# DTMF.net
KiCad netlist of a schematic drawn in Altium Designer
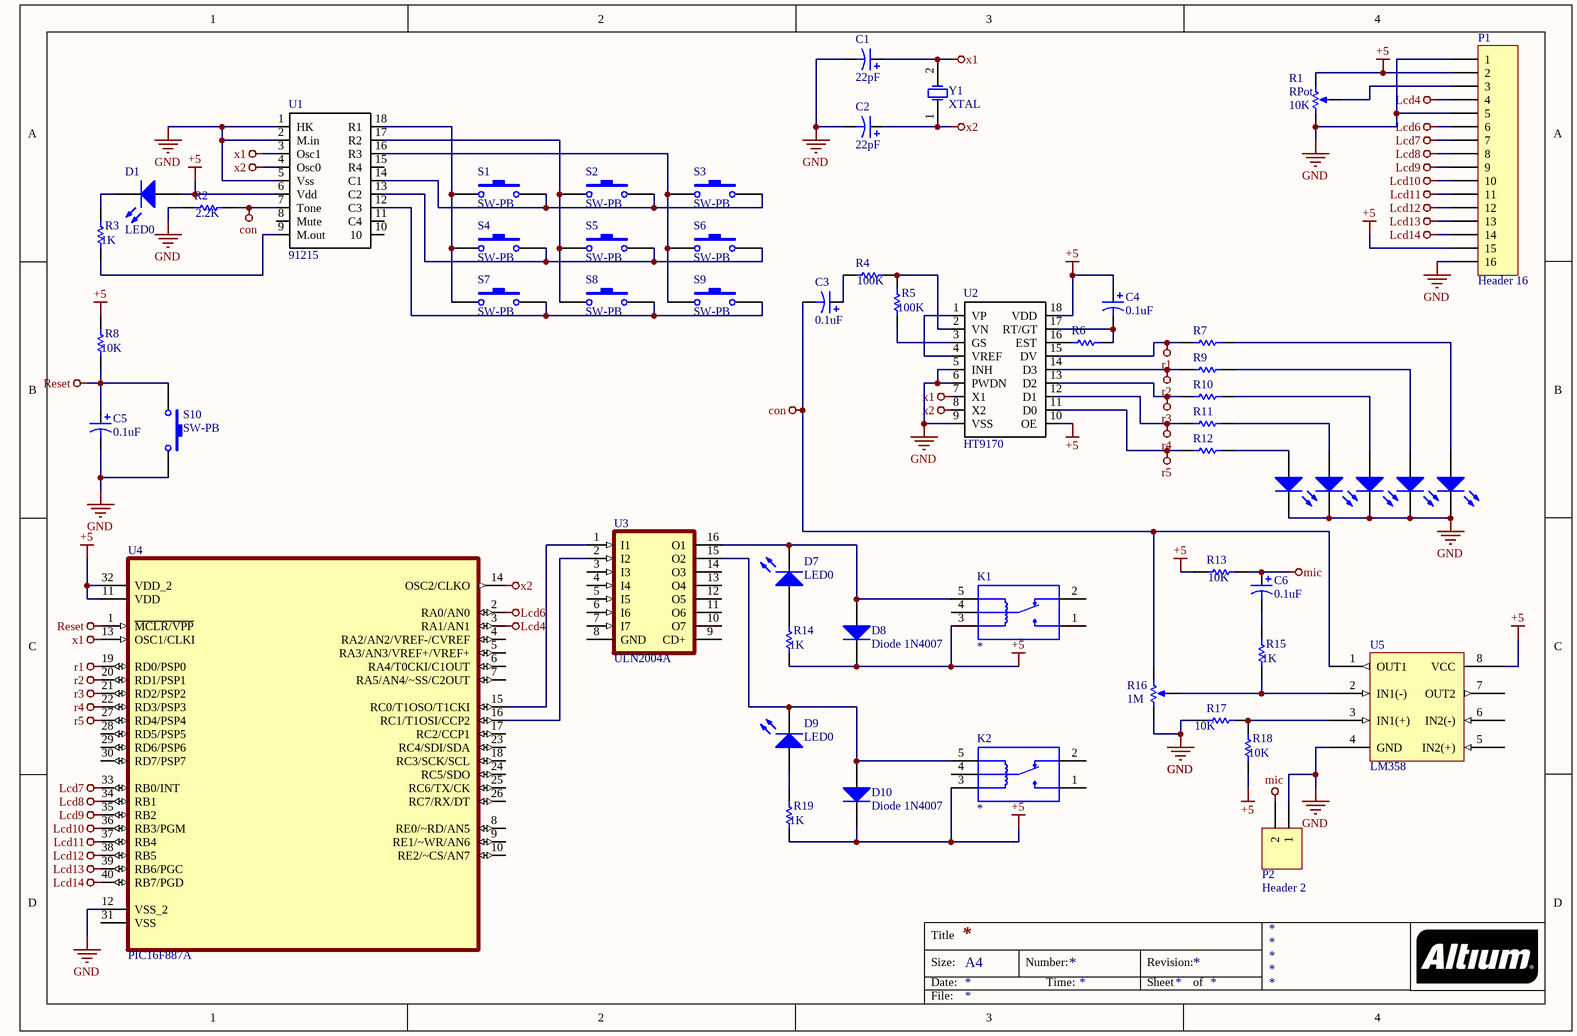
[diagram p0: DTMF.SchDoc]

(export (version "E")
  (design (tool "Eeschema 10.0.6"))
  (components
    (comp (ref "C1")
      (value "22pF")
      (footprint "capacitor")
      (fields (field (name "Comment") "cap"))
      (libsource (lib "capacitor") (part "cap"))
    )
    (comp (ref "C2")
      (value "22pF")
      (footprint "capacitor")
      (fields (field (name "Comment") "cap"))
      (libsource (lib "capacitor") (part "cap"))
    )
    (comp (ref "C3")
      (value "0.1uF")
      (footprint "capacitor")
      (fields (field (name "Comment") "cap"))
      (libsource (lib "capacitor") (part "cap"))
    )
    (comp (ref "C4")
      (value "0.1uF")
      (footprint "capacitor")
      (fields (field (name "Comment") "cap"))
      (libsource (lib "capacitor") (part "cap"))
    )
    (comp (ref "C5")
      (value "0.1uF")
      (footprint "capacitor")
      (fields (field (name "Comment") "cap"))
      (libsource (lib "capacitor") (part "cap"))
    )
    (comp (ref "C6")
      (value "0.1uF")
      (footprint "capacitor")
      (fields (field (name "Comment") "cap"))
      (libsource (lib "capacitor") (part "cap"))
    )
    (comp (ref "D1")
      (value "LED0")
      (footprint "LED-0")
      (description "Typical INFRARED GaAs LED")
      (fields (field (name "PUBLISHER") "Altium Limited"))
      (libsource (lib "Miscellaneous Devices") (part "LED0"))
    )
    (comp (ref "D2")
      (value "LED0")
      (footprint "LED-0")
      (description "Typical INFRARED GaAs LED")
      (fields (field (name "PUBLISHER") "Altium Limited"))
      (libsource (lib "Miscellaneous Devices") (part "LED0"))
    )
    (comp (ref "D3")
      (value "LED0")
      (footprint "LED-0")
      (description "Typical INFRARED GaAs LED")
      (fields (field (name "PUBLISHER") "Altium Limited"))
      (libsource (lib "Miscellaneous Devices") (part "LED0"))
    )
    (comp (ref "D4")
      (value "LED0")
      (footprint "LED-0")
      (description "Typical INFRARED GaAs LED")
      (fields (field (name "PUBLISHER") "Altium Limited"))
      (libsource (lib "Miscellaneous Devices") (part "LED0"))
    )
    (comp (ref "D5")
      (value "LED0")
      (footprint "LED-0")
      (description "Typical INFRARED GaAs LED")
      (fields (field (name "PUBLISHER") "Altium Limited"))
      (libsource (lib "Miscellaneous Devices") (part "LED0"))
    )
    (comp (ref "D6")
      (value "LED0")
      (footprint "LED-0")
      (description "Typical INFRARED GaAs LED")
      (fields (field (name "PUBLISHER") "Altium Limited"))
      (libsource (lib "Miscellaneous Devices") (part "LED0"))
    )
    (comp (ref "D7")
      (value "LED0")
      (footprint "LED-0")
      (description "Typical INFRARED GaAs LED")
      (fields (field (name "PUBLISHER") "Altium Limited"))
      (libsource (lib "Miscellaneous Devices") (part "LED0"))
    )
    (comp (ref "D8")
      (value "Diode 1N4007")
      (footprint "DO-41")
      (description "1 Amp General Purpose Rectifier")
      (fields (field (name "PUBLISHER") "Altium Limited"))
      (libsource (lib "Miscellaneous Devices") (part "Diode 1N4007"))
    )
    (comp (ref "D9")
      (value "LED0")
      (footprint "LED-0")
      (description "Typical INFRARED GaAs LED")
      (fields (field (name "PUBLISHER") "Altium Limited"))
      (libsource (lib "Miscellaneous Devices") (part "LED0"))
    )
    (comp (ref "D10")
      (value "Diode 1N4007")
      (footprint "DO-41")
      (description "1 Amp General Purpose Rectifier")
      (fields (field (name "PUBLISHER") "Altium Limited"))
      (libsource (lib "Miscellaneous Devices") (part "Diode 1N4007"))
    )
    (comp (ref "K1")
      (value "1-1721150-0")
      (footprint "SnapEDApcb:RELAY_ORWH-SH-105D1F,000")
      (description "Electromechanical Relay 5VDC 15A SPDT __ 19.2mm 15.5mm 15mm__ THT General Purpose Relay")
      (fields
        (field (name "MP") "ORWH-SH-105D1F,000")
        (field (name "MF") "TE Connectivity")
        (field (name "COMMENT_1") "*")
      )
      (libsource (lib "SnapEDAsch") (part "ORWH-SH-105D1F,000"))
    )
    (comp (ref "K2")
      (value "1-1721150-0")
      (footprint "SnapEDApcb:RELAY_ORWH-SH-105D1F,000")
      (description "Electromechanical Relay 5VDC 15A SPDT __ 19.2mm 15.5mm 15mm__ THT General Purpose Relay")
      (fields
        (field (name "MP") "ORWH-SH-105D1F,000")
        (field (name "MF") "TE Connectivity")
        (field (name "COMMENT_1") "*")
      )
      (libsource (lib "SnapEDAsch") (part "ORWH-SH-105D1F,000"))
    )
    (comp (ref "P1")
      (value "Header 16")
      (footprint "HDR1X16")
      (description "Header, 16-Pin")
      (fields (field (name "PUBLISHER") "Altium Limited"))
      (libsource (lib "Miscellaneous Connectors") (part "Header 16"))
    )
    (comp (ref "P2")
      (value "Header 2")
      (footprint "HDR1X2")
      (description "Header, 2-Pin")
      (fields (field (name "PUBLISHER") "Altium Limited"))
      (libsource (lib "Miscellaneous Connectors") (part "Header 2"))
    )
    (comp (ref "R1")
      (value "RPot")
      (footprint "VR5")
      (description "Potentiometer")
      (fields (field (name "ALTIUM_VALUE") "10K") (field (name "PUBLISHER") "Altium Limited"))
      (libsource (lib "Miscellaneous Devices") (part "RPot"))
    )
    (comp (ref "R2")
      (value "2.2K")
      (footprint "AXIAL-0.3")
      (description "Resistor")
      (fields (field (name "Comment") "Res1") (field (name "PUBLISHER") "Altium Limited"))
      (libsource (lib "Miscellaneous Devices") (part "Res1"))
    )
    (comp (ref "R3")
      (value "1K")
      (footprint "AXIAL-0.3")
      (description "Resistor")
      (fields (field (name "Comment") "Res1") (field (name "PUBLISHER") "Altium Limited"))
      (libsource (lib "Miscellaneous Devices") (part "Res1"))
    )
    (comp (ref "R4")
      (value "100K")
      (footprint "AXIAL-0.3")
      (description "Resistor")
      (fields (field (name "Comment") "Res1") (field (name "PUBLISHER") "Altium Limited"))
      (libsource (lib "Miscellaneous Devices") (part "Res1"))
    )
    (comp (ref "R5")
      (value "100K")
      (footprint "AXIAL-0.3")
      (description "Resistor")
      (fields (field (name "Comment") "Res1") (field (name "PUBLISHER") "Altium Limited"))
      (libsource (lib "Miscellaneous Devices") (part "Res1"))
    )
    (comp (ref "R6")
      (value "Res1")
      (footprint "AXIAL-0.3")
      (description "Resistor")
      (fields (field (name "PUBLISHER") "Altium Limited"))
      (libsource (lib "Miscellaneous Devices") (part "Res1"))
    )
    (comp (ref "R7")
      (value "Res1")
      (footprint "AXIAL-0.3")
      (description "Resistor")
      (fields (field (name "PUBLISHER") "Altium Limited"))
      (libsource (lib "Miscellaneous Devices") (part "Res1"))
    )
    (comp (ref "R8")
      (value "10K")
      (footprint "AXIAL-0.3")
      (description "Resistor")
      (fields (field (name "Comment") "Res1") (field (name "PUBLISHER") "Altium Limited"))
      (libsource (lib "Miscellaneous Devices") (part "Res1"))
    )
    (comp (ref "R9")
      (value "Res1")
      (footprint "AXIAL-0.3")
      (description "Resistor")
      (fields (field (name "PUBLISHER") "Altium Limited"))
      (libsource (lib "Miscellaneous Devices") (part "Res1"))
    )
    (comp (ref "R10")
      (value "Res1")
      (footprint "AXIAL-0.3")
      (description "Resistor")
      (fields (field (name "PUBLISHER") "Altium Limited"))
      (libsource (lib "Miscellaneous Devices") (part "Res1"))
    )
    (comp (ref "R11")
      (value "Res1")
      (footprint "AXIAL-0.3")
      (description "Resistor")
      (fields (field (name "PUBLISHER") "Altium Limited"))
      (libsource (lib "Miscellaneous Devices") (part "Res1"))
    )
    (comp (ref "R12")
      (value "Res1")
      (footprint "AXIAL-0.3")
      (description "Resistor")
      (fields (field (name "PUBLISHER") "Altium Limited"))
      (libsource (lib "Miscellaneous Devices") (part "Res1"))
    )
    (comp (ref "R13")
      (value "10K")
      (footprint "AXIAL-0.3")
      (description "Resistor")
      (fields (field (name "Comment") "Res1") (field (name "PUBLISHER") "Altium Limited"))
      (libsource (lib "Miscellaneous Devices") (part "Res1"))
    )
    (comp (ref "R14")
      (value "1K")
      (footprint "AXIAL-0.3")
      (description "Resistor")
      (fields (field (name "Comment") "Res1") (field (name "PUBLISHER") "Altium Limited"))
      (libsource (lib "Miscellaneous Devices") (part "Res1"))
    )
    (comp (ref "R15")
      (value "1K")
      (footprint "AXIAL-0.3")
      (description "Resistor")
      (fields (field (name "Comment") "Res1") (field (name "PUBLISHER") "Altium Limited"))
      (libsource (lib "Miscellaneous Devices") (part "Res1"))
    )
    (comp (ref "R16")
      (value "1M")
      (footprint "VR5")
      (description "Potentiometer")
      (fields (field (name "Comment") "RPot") (field (name "PUBLISHER") "Altium Limited"))
      (libsource (lib "Miscellaneous Devices") (part "RPot"))
    )
    (comp (ref "R17")
      (value "10K")
      (footprint "AXIAL-0.3")
      (description "Resistor")
      (fields (field (name "Comment") "Res1") (field (name "PUBLISHER") "Altium Limited"))
      (libsource (lib "Miscellaneous Devices") (part "Res1"))
    )
    (comp (ref "R18")
      (value "10K")
      (footprint "AXIAL-0.3")
      (description "Resistor")
      (fields (field (name "Comment") "Res1") (field (name "PUBLISHER") "Altium Limited"))
      (libsource (lib "Miscellaneous Devices") (part "Res1"))
    )
    (comp (ref "R19")
      (value "1K")
      (footprint "AXIAL-0.3")
      (description "Resistor")
      (fields (field (name "Comment") "Res1") (field (name "PUBLISHER") "Altium Limited"))
      (libsource (lib "Miscellaneous Devices") (part "Res1"))
    )
    (comp (ref "S1")
      (value "SW-PB")
      (footprint "SPST-2")
      (description "Switch")
      (fields (field (name "PUBLISHER") "Altium Limited"))
      (libsource (lib "Miscellaneous Devices") (part "SW-PB"))
    )
    (comp (ref "S2")
      (value "SW-PB")
      (footprint "SPST-2")
      (description "Switch")
      (fields (field (name "PUBLISHER") "Altium Limited"))
      (libsource (lib "Miscellaneous Devices") (part "SW-PB"))
    )
    (comp (ref "S3")
      (value "SW-PB")
      (footprint "SPST-2")
      (description "Switch")
      (fields (field (name "PUBLISHER") "Altium Limited"))
      (libsource (lib "Miscellaneous Devices") (part "SW-PB"))
    )
    (comp (ref "S4")
      (value "SW-PB")
      (footprint "SPST-2")
      (description "Switch")
      (fields (field (name "PUBLISHER") "Altium Limited"))
      (libsource (lib "Miscellaneous Devices") (part "SW-PB"))
    )
    (comp (ref "S5")
      (value "SW-PB")
      (footprint "SPST-2")
      (description "Switch")
      (fields (field (name "PUBLISHER") "Altium Limited"))
      (libsource (lib "Miscellaneous Devices") (part "SW-PB"))
    )
    (comp (ref "S6")
      (value "SW-PB")
      (footprint "SPST-2")
      (description "Switch")
      (fields (field (name "PUBLISHER") "Altium Limited"))
      (libsource (lib "Miscellaneous Devices") (part "SW-PB"))
    )
    (comp (ref "S7")
      (value "SW-PB")
      (footprint "SPST-2")
      (description "Switch")
      (fields (field (name "PUBLISHER") "Altium Limited"))
      (libsource (lib "Miscellaneous Devices") (part "SW-PB"))
    )
    (comp (ref "S8")
      (value "SW-PB")
      (footprint "SPST-2")
      (description "Switch")
      (fields (field (name "PUBLISHER") "Altium Limited"))
      (libsource (lib "Miscellaneous Devices") (part "SW-PB"))
    )
    (comp (ref "S9")
      (value "SW-PB")
      (footprint "SPST-2")
      (description "Switch")
      (fields (field (name "PUBLISHER") "Altium Limited"))
      (libsource (lib "Miscellaneous Devices") (part "SW-PB"))
    )
    (comp (ref "S10")
      (value "SW-PB")
      (footprint "SPST-2")
      (description "Switch")
      (fields (field (name "PUBLISHER") "Altium Limited"))
      (libsource (lib "Miscellaneous Devices") (part "SW-PB"))
    )
    (comp (ref "U1") (value "91215") (footprint "HT9170") (libsource (lib "Schlib1") (part "91215")))
    (comp (ref "U2")
      (value "HT9170")
      (footprint "HT9170")
      (fields (field (name "MF") "Holtek") (field (name "MP") "HT9170B"))
      (libsource (lib "HT9170") (part "HT9170"))
    )
    (comp (ref "U3")
      (value "ULN2004A")
      (footprint "ULN2004A:ULN2004A")
      (fields (field (name "MF") "STMicroelectronics"))
      (libsource (lib "SnapEDAsch") (part "ULN2004A"))
    )
    (comp (ref "U4")
      (value "PIC16F887A")
      (footprint "PIC16F887A")
      (description "PIC PICÂ® 16F Microcontroller IC 8-Bit 20MHz 14KB _8K x 14_ FLASH 40-PDIP")
      (fields (field (name "MP") "PIC16F877A-I/P") (field (name "MF") "Microchip"))
      (libsource (lib "SnapEDAsch") (part "PIC16F877A-I/P"))
    )
    (comp (ref "U5") (value "LM358") (footprint "LM358") (libsource (lib "LM358") (part "LM358")))
    (comp (ref "Y1")
      (value "XTAL")
      (footprint "R38")
      (description "Crystal Oscillator")
      (fields (field (name "PUBLISHER") "Altium Limited"))
      (libsource (lib "Miscellaneous Devices") (part "XTAL"))
    )
  )
  (nets
    (net (code "1") (name "+5") (class "Default")
      (node (ref "C4") (pin "1") (pinfunction "1_1") (pintype "passive"))
      (node (ref "D1") (pin "1") (pinfunction "A_1") (pintype "passive"))
      (node (ref "D10") (pin "2") (pinfunction "K_2") (pintype "passive"))
      (node (ref "D8") (pin "2") (pinfunction "K_2") (pintype "passive"))
      (node (ref "K1") (pin "3") (pinfunction "C1_3") (pintype "passive"))
      (node (ref "K2") (pin "3") (pinfunction "C1_3") (pintype "passive"))
      (node (ref "P1") (pin "15") (pinfunction "15_15") (pintype "passive"))
      (node (ref "P1") (pin "2") (pinfunction "2_2") (pintype "passive"))
      (node (ref "R1") (pin "2") (pinfunction "BOT_2") (pintype "passive"))
      (node (ref "R13") (pin "1") (pinfunction "1_1") (pintype "passive"))
      (node (ref "R14") (pin "1") (pinfunction "1_1") (pintype "passive"))
      (node (ref "R18") (pin "1") (pinfunction "1_1") (pintype "passive"))
      (node (ref "R19") (pin "1") (pinfunction "1_1") (pintype "passive"))
      (node (ref "R8") (pin "2") (pinfunction "2_2") (pintype "passive"))
      (node (ref "U1") (pin "6") (pinfunction "Vdd_6") (pintype "passive"))
      (node (ref "U2") (pin "10") (pinfunction "OE_10") (pintype "bidirectional"))
      (node (ref "U2") (pin "18") (pinfunction "VDD_18") (pintype "power_in"))
      (node (ref "U4") (pin "11") (pinfunction "VDD_11") (pintype "power_in"))
      (node (ref "U4") (pin "32") (pinfunction "VDD_2_32") (pintype "power_in"))
      (node (ref "U5") (pin "8") (pinfunction "VCC_8") (pintype "passive"))
    )
    (net (code "2") (name "GND") (class "Default")
      (node (ref "C1") (pin "2") (pinfunction "2_2") (pintype "passive"))
      (node (ref "C2") (pin "2") (pinfunction "2_2") (pintype "passive"))
      (node (ref "C5") (pin "2") (pinfunction "2_2") (pintype "passive"))
      (node (ref "D2") (pin "2") (pinfunction "K_2") (pintype "passive"))
      (node (ref "D3") (pin "2") (pinfunction "K_2") (pintype "passive"))
      (node (ref "D4") (pin "2") (pinfunction "K_2") (pintype "passive"))
      (node (ref "D5") (pin "2") (pinfunction "K_2") (pintype "passive"))
      (node (ref "D6") (pin "2") (pinfunction "K_2") (pintype "passive"))
      (node (ref "P1") (pin "1") (pinfunction "1_1") (pintype "passive"))
      (node (ref "P1") (pin "16") (pinfunction "16_16") (pintype "passive"))
      (node (ref "P1") (pin "5") (pinfunction "5_5") (pintype "passive"))
      (node (ref "P2") (pin "1") (pinfunction "1_1") (pintype "passive"))
      (node (ref "R1") (pin "1") (pinfunction "TOP_1") (pintype "passive"))
      (node (ref "R16") (pin "1") (pinfunction "TOP_1") (pintype "passive"))
      (node (ref "R17") (pin "1") (pinfunction "1_1") (pintype "passive"))
      (node (ref "R2") (pin "1") (pinfunction "1_1") (pintype "passive"))
      (node (ref "S10") (pin "2") (pinfunction "2_2") (pintype "passive"))
      (node (ref "U1") (pin "1") (pinfunction "HK_1") (pintype "passive"))
      (node (ref "U1") (pin "2") (pinfunction "M.in_2") (pintype "passive"))
      (node (ref "U1") (pin "5") (pinfunction "Vss_5") (pintype "passive"))
      (node (ref "U2") (pin "5") (pinfunction "INH_5") (pintype "bidirectional"))
      (node (ref "U2") (pin "6") (pinfunction "PWDN_6") (pintype "bidirectional"))
      (node (ref "U2") (pin "9") (pinfunction "VSS_9") (pintype "power_in"))
      (node (ref "U4") (pin "12") (pinfunction "VSS_2_12") (pintype "power_in"))
      (node (ref "U5") (pin "4") (pinfunction "GND_4") (pintype "passive"))
    )
    (net (code "3") (name "Lcd4") (class "Default")
      (node (ref "P1") (pin "4") (pinfunction "4_4") (pintype "passive"))
      (node (ref "U4") (pin "3") (pinfunction "RA1/AN1_3") (pintype "bidirectional"))
    )
    (net (code "4") (name "Lcd6") (class "Default")
      (node (ref "P1") (pin "6") (pinfunction "6_6") (pintype "passive"))
      (node (ref "U4") (pin "2") (pinfunction "RA0/AN0_2") (pintype "bidirectional"))
    )
    (net (code "5") (name "Lcd7") (class "Default")
      (node (ref "P1") (pin "7") (pinfunction "7_7") (pintype "passive"))
      (node (ref "U4") (pin "33") (pinfunction "RB0/INT_33") (pintype "bidirectional"))
    )
    (net (code "6") (name "Lcd8") (class "Default")
      (node (ref "P1") (pin "8") (pinfunction "8_8") (pintype "passive"))
      (node (ref "U4") (pin "34") (pinfunction "RB1_34") (pintype "bidirectional"))
    )
    (net (code "7") (name "Lcd9") (class "Default")
      (node (ref "P1") (pin "9") (pinfunction "9_9") (pintype "passive"))
      (node (ref "U4") (pin "35") (pinfunction "RB2_35") (pintype "bidirectional"))
    )
    (net (code "8") (name "Lcd10") (class "Default")
      (node (ref "P1") (pin "10") (pinfunction "10_10") (pintype "passive"))
      (node (ref "U4") (pin "36") (pinfunction "RB3/PGM_36") (pintype "bidirectional"))
    )
    (net (code "9") (name "Lcd11") (class "Default")
      (node (ref "P1") (pin "11") (pinfunction "11_11") (pintype "passive"))
      (node (ref "U4") (pin "37") (pinfunction "RB4_37") (pintype "bidirectional"))
    )
    (net (code "10") (name "Lcd12") (class "Default")
      (node (ref "P1") (pin "12") (pinfunction "12_12") (pintype "passive"))
      (node (ref "U4") (pin "38") (pinfunction "RB5_38") (pintype "bidirectional"))
    )
    (net (code "11") (name "Lcd13") (class "Default")
      (node (ref "P1") (pin "13") (pinfunction "13_13") (pintype "passive"))
      (node (ref "U4") (pin "39") (pinfunction "RB6/PGC_39") (pintype "bidirectional"))
    )
    (net (code "12") (name "Lcd14") (class "Default")
      (node (ref "P1") (pin "14") (pinfunction "14_14") (pintype "passive"))
      (node (ref "U4") (pin "40") (pinfunction "RB7/PGD_40") (pintype "bidirectional"))
    )
    (net (code "13") (name "Net-(C3-Pad1)") (class "Default")
      (node (ref "C3") (pin "1") (pinfunction "1_1") (pintype "passive"))
      (node (ref "R4") (pin "1") (pinfunction "1_1") (pintype "passive"))
    )
    (net (code "14") (name "Net-(C6-Pad2)") (class "Default")
      (node (ref "C6") (pin "2") (pinfunction "2_2") (pintype "passive"))
      (node (ref "R15") (pin "2") (pinfunction "2_2") (pintype "passive"))
    )
    (net (code "15") (name "Net-(D1-K)") (class "Default")
      (node (ref "D1") (pin "2") (pinfunction "K_2") (pintype "passive"))
      (node (ref "R3") (pin "2") (pinfunction "2_2") (pintype "passive"))
    )
    (net (code "16") (name "Net-(D2-A)") (class "Default")
      (node (ref "D2") (pin "1") (pinfunction "A_1") (pintype "passive"))
      (node (ref "R12") (pin "2") (pinfunction "2_2") (pintype "passive"))
    )
    (net (code "17") (name "Net-(D3-A)") (class "Default")
      (node (ref "D3") (pin "1") (pinfunction "A_1") (pintype "passive"))
      (node (ref "R11") (pin "2") (pinfunction "2_2") (pintype "passive"))
    )
    (net (code "18") (name "Net-(D4-A)") (class "Default")
      (node (ref "D4") (pin "1") (pinfunction "A_1") (pintype "passive"))
      (node (ref "R10") (pin "2") (pinfunction "2_2") (pintype "passive"))
    )
    (net (code "19") (name "Net-(D5-A)") (class "Default")
      (node (ref "D5") (pin "1") (pinfunction "A_1") (pintype "passive"))
      (node (ref "R9") (pin "2") (pinfunction "2_2") (pintype "passive"))
    )
    (net (code "20") (name "Net-(D6-A)") (class "Default")
      (node (ref "D6") (pin "1") (pinfunction "A_1") (pintype "passive"))
      (node (ref "R7") (pin "2") (pinfunction "2_2") (pintype "passive"))
    )
    (net (code "21") (name "Net-(D7-A)") (class "Default")
      (node (ref "D7") (pin "1") (pinfunction "A_1") (pintype "passive"))
      (node (ref "R14") (pin "2") (pinfunction "2_2") (pintype "passive"))
    )
    (net (code "22") (name "Net-(D7-K)") (class "Default")
      (node (ref "D7") (pin "2") (pinfunction "K_2") (pintype "passive"))
      (node (ref "D8") (pin "1") (pinfunction "A_1") (pintype "passive"))
      (node (ref "K1") (pin "5") (pinfunction "C2_5") (pintype "passive"))
      (node (ref "U3") (pin "16") (pinfunction "O1_16") (pintype "open_collector"))
    )
    (net (code "23") (name "Net-(D9-A)") (class "Default")
      (node (ref "D9") (pin "1") (pinfunction "A_1") (pintype "passive"))
      (node (ref "R19") (pin "2") (pinfunction "2_2") (pintype "passive"))
    )
    (net (code "24") (name "Net-(D10-A)") (class "Default")
      (node (ref "D10") (pin "1") (pinfunction "A_1") (pintype "passive"))
      (node (ref "D9") (pin "2") (pinfunction "K_2") (pintype "passive"))
      (node (ref "K2") (pin "5") (pinfunction "C2_5") (pintype "passive"))
      (node (ref "U3") (pin "15") (pinfunction "O2_15") (pintype "open_collector"))
    )
    (net (code "25") (name "Net-(R1-TAP)") (class "Default")
      (node (ref "P1") (pin "3") (pinfunction "3_3") (pintype "passive"))
      (node (ref "R1") (pin "3") (pinfunction "TAP_3") (pintype "passive"))
    )
    (net (code "26") (name "Net-(R16-TAP)") (class "Default")
      (node (ref "R15") (pin "1") (pinfunction "1_1") (pintype "passive"))
      (node (ref "R16") (pin "3") (pinfunction "TAP_3") (pintype "passive"))
      (node (ref "U5") (pin "2") (pinfunction "IN1(-)_2") (pintype "input"))
    )
    (net (code "27") (name "Net-(U1-C1)") (class "Default")
      (node (ref "S1") (pin "2") (pinfunction "2_2") (pintype "passive"))
      (node (ref "S2") (pin "2") (pinfunction "2_2") (pintype "passive"))
      (node (ref "S3") (pin "2") (pinfunction "2_2") (pintype "passive"))
      (node (ref "U1") (pin "14") (pinfunction "C1_14") (pintype "passive"))
    )
    (net (code "28") (name "Net-(U1-C2)") (class "Default")
      (node (ref "S4") (pin "2") (pinfunction "2_2") (pintype "passive"))
      (node (ref "S5") (pin "2") (pinfunction "2_2") (pintype "passive"))
      (node (ref "S6") (pin "2") (pinfunction "2_2") (pintype "passive"))
      (node (ref "U1") (pin "13") (pinfunction "C2_13") (pintype "passive"))
    )
    (net (code "29") (name "Net-(U1-C3)") (class "Default")
      (node (ref "S7") (pin "2") (pinfunction "2_2") (pintype "passive"))
      (node (ref "S8") (pin "2") (pinfunction "2_2") (pintype "passive"))
      (node (ref "S9") (pin "2") (pinfunction "2_2") (pintype "passive"))
      (node (ref "U1") (pin "12") (pinfunction "C3_12") (pintype "passive"))
    )
    (net (code "30") (name "Net-(U1-M.out)") (class "Default")
      (node (ref "R3") (pin "1") (pinfunction "1_1") (pintype "passive"))
      (node (ref "U1") (pin "9") (pinfunction "M.out_9") (pintype "power_in"))
    )
    (net (code "31") (name "Net-(U1-R1)") (class "Default")
      (node (ref "S1") (pin "1") (pinfunction "1_1") (pintype "passive"))
      (node (ref "S4") (pin "1") (pinfunction "1_1") (pintype "passive"))
      (node (ref "S7") (pin "1") (pinfunction "1_1") (pintype "passive"))
      (node (ref "U1") (pin "18") (pinfunction "R1_18") (pintype "power_in"))
    )
    (net (code "32") (name "Net-(U1-R2)") (class "Default")
      (node (ref "S2") (pin "1") (pinfunction "1_1") (pintype "passive"))
      (node (ref "S5") (pin "1") (pinfunction "1_1") (pintype "passive"))
      (node (ref "S8") (pin "1") (pinfunction "1_1") (pintype "passive"))
      (node (ref "U1") (pin "17") (pinfunction "R2_17") (pintype "passive"))
    )
    (net (code "33") (name "Net-(U1-R3)") (class "Default")
      (node (ref "S3") (pin "1") (pinfunction "1_1") (pintype "passive"))
      (node (ref "S6") (pin "1") (pinfunction "1_1") (pintype "passive"))
      (node (ref "S9") (pin "1") (pinfunction "1_1") (pintype "passive"))
      (node (ref "U1") (pin "16") (pinfunction "R3_16") (pintype "passive"))
    )
    (net (code "34") (name "Net-(U2-EST)") (class "Default")
      (node (ref "R6") (pin "1") (pinfunction "1_1") (pintype "passive"))
      (node (ref "U2") (pin "16") (pinfunction "EST_16") (pintype "bidirectional"))
    )
    (net (code "35") (name "Net-(U2-GS)") (class "Default")
      (node (ref "R5") (pin "1") (pinfunction "1_1") (pintype "passive"))
      (node (ref "U2") (pin "3") (pinfunction "GS_3") (pintype "bidirectional"))
    )
    (net (code "36") (name "Net-(U2-RT{slash}GT)") (class "Default")
      (node (ref "C4") (pin "2") (pinfunction "2_2") (pintype "passive"))
      (node (ref "R6") (pin "2") (pinfunction "2_2") (pintype "passive"))
      (node (ref "U2") (pin "17") (pinfunction "RT/GT_17") (pintype "bidirectional"))
    )
    (net (code "37") (name "Net-(U2-VN)") (class "Default")
      (node (ref "R4") (pin "2") (pinfunction "2_2") (pintype "passive"))
      (node (ref "R5") (pin "2") (pinfunction "2_2") (pintype "passive"))
      (node (ref "U2") (pin "2") (pinfunction "VN_2") (pintype "bidirectional"))
    )
    (net (code "38") (name "Net-(U2-VP)") (class "Default")
      (node (ref "U2") (pin "1") (pinfunction "VP_1") (pintype "bidirectional"))
      (node (ref "U2") (pin "4") (pinfunction "VREF_4") (pintype "bidirectional"))
    )
    (net (code "39") (name "Net-(U3-I1)") (class "Default")
      (node (ref "U3") (pin "1") (pinfunction "I1_1") (pintype "input"))
      (node (ref "U4") (pin "15") (pinfunction "RC0/T1OSO/T1CKI_15") (pintype "bidirectional"))
    )
    (net (code "40") (name "Net-(U3-I2)") (class "Default")
      (node (ref "U3") (pin "2") (pinfunction "I2_2") (pintype "input"))
      (node (ref "U4") (pin "16") (pinfunction "RC1/T1OSI/CCP2_16") (pintype "bidirectional"))
    )
    (net (code "41") (name "Net-(U5-IN1(+))") (class "Default")
      (node (ref "R17") (pin "2") (pinfunction "2_2") (pintype "passive"))
      (node (ref "R18") (pin "2") (pinfunction "2_2") (pintype "passive"))
      (node (ref "U5") (pin "3") (pinfunction "IN1(+)_3") (pintype "input"))
    )
    (net (code "42") (name "Reset") (class "Default")
      (node (ref "C5") (pin "1") (pinfunction "1_1") (pintype "passive"))
      (node (ref "R8") (pin "1") (pinfunction "1_1") (pintype "passive"))
      (node (ref "S10") (pin "1") (pinfunction "1_1") (pintype "passive"))
      (node (ref "U4") (pin "1") (pinfunction "~{MCLR/VPP}_1") (pintype "input"))
    )
    (net (code "43") (name "con") (class "Default")
      (node (ref "C3") (pin "2") (pinfunction "2_2") (pintype "passive"))
      (node (ref "R16") (pin "2") (pinfunction "BOT_2") (pintype "passive"))
      (node (ref "R2") (pin "2") (pinfunction "2_2") (pintype "passive"))
      (node (ref "U1") (pin "7") (pinfunction "Tone_7") (pintype "passive"))
      (node (ref "U5") (pin "1") (pinfunction "OUT1_1") (pintype "output"))
    )
    (net (code "44") (name "mic") (class "Default")
      (node (ref "C6") (pin "1") (pinfunction "1_1") (pintype "passive"))
      (node (ref "P2") (pin "2") (pinfunction "2_2") (pintype "passive"))
      (node (ref "R13") (pin "2") (pinfunction "2_2") (pintype "passive"))
    )
    (net (code "45") (name "r1") (class "Default")
      (node (ref "R7") (pin "1") (pinfunction "1_1") (pintype "passive"))
      (node (ref "U2") (pin "15") (pinfunction "DV_15") (pintype "bidirectional"))
      (node (ref "U4") (pin "19") (pinfunction "RD0/PSP0_19") (pintype "bidirectional"))
    )
    (net (code "46") (name "r2") (class "Default")
      (node (ref "R9") (pin "1") (pinfunction "1_1") (pintype "passive"))
      (node (ref "U2") (pin "14") (pinfunction "D3_14") (pintype "bidirectional"))
      (node (ref "U4") (pin "20") (pinfunction "RD1/PSP1_20") (pintype "bidirectional"))
    )
    (net (code "47") (name "r3") (class "Default")
      (node (ref "R10") (pin "1") (pinfunction "1_1") (pintype "passive"))
      (node (ref "U2") (pin "13") (pinfunction "D2_13") (pintype "bidirectional"))
      (node (ref "U4") (pin "21") (pinfunction "RD2/PSP2_21") (pintype "bidirectional"))
    )
    (net (code "48") (name "r4") (class "Default")
      (node (ref "R11") (pin "1") (pinfunction "1_1") (pintype "passive"))
      (node (ref "U2") (pin "12") (pinfunction "D1_12") (pintype "bidirectional"))
      (node (ref "U4") (pin "22") (pinfunction "RD3/PSP3_22") (pintype "bidirectional"))
    )
    (net (code "49") (name "r5") (class "Default")
      (node (ref "R12") (pin "1") (pinfunction "1_1") (pintype "passive"))
      (node (ref "U2") (pin "11") (pinfunction "D0_11") (pintype "bidirectional"))
      (node (ref "U4") (pin "27") (pinfunction "RD4/PSP4_27") (pintype "bidirectional"))
    )
    (net (code "50") (name "unconnected-(K1-C-Pad4)") (class "Default")
      (node (ref "K1") (pin "4") (pinfunction "C_4") (pintype "passive"))
    )
    (net (code "51") (name "unconnected-(K1-NC-Pad2)") (class "Default")
      (node (ref "K1") (pin "2") (pinfunction "NC_2") (pintype "passive"))
    )
    (net (code "52") (name "unconnected-(K1-NO-Pad1)") (class "Default")
      (node (ref "K1") (pin "1") (pinfunction "NO_1") (pintype "passive"))
    )
    (net (code "53") (name "unconnected-(K2-C-Pad4)") (class "Default")
      (node (ref "K2") (pin "4") (pinfunction "C_4") (pintype "passive"))
    )
    (net (code "54") (name "unconnected-(K2-NC-Pad2)") (class "Default")
      (node (ref "K2") (pin "2") (pinfunction "NC_2") (pintype "passive"))
    )
    (net (code "55") (name "unconnected-(K2-NO-Pad1)") (class "Default")
      (node (ref "K2") (pin "1") (pinfunction "NO_1") (pintype "passive"))
    )
    (net (code "56") (name "unconnected-(U1-C4-Pad11)") (class "Default")
      (node (ref "U1") (pin "11") (pinfunction "C4_11") (pintype "passive"))
    )
    (net (code "57") (name "unconnected-(U1-Mute-Pad8)") (class "Default")
      (node (ref "U1") (pin "8") (pinfunction "Mute_8") (pintype "passive"))
    )
    (net (code "58") (name "unconnected-(U1-Pad10)") (class "Default")
      (node (ref "U1") (pin "10") (pinfunction "10_10") (pintype "passive"))
    )
    (net (code "59") (name "unconnected-(U1-R4-Pad15)") (class "Default")
      (node (ref "U1") (pin "15") (pinfunction "R4_15") (pintype "passive"))
    )
    (net (code "60") (name "unconnected-(U3-CD+-Pad9)") (class "Default")
      (node (ref "U3") (pin "9") (pinfunction "CD+_9") (pintype "passive"))
    )
    (net (code "61") (name "unconnected-(U3-GND-Pad8)") (class "Default")
      (node (ref "U3") (pin "8") (pinfunction "GND_8") (pintype "power_in"))
    )
    (net (code "62") (name "unconnected-(U3-I3-Pad3)") (class "Default")
      (node (ref "U3") (pin "3") (pinfunction "I3_3") (pintype "input"))
    )
    (net (code "63") (name "unconnected-(U3-I4-Pad4)") (class "Default")
      (node (ref "U3") (pin "4") (pinfunction "I4_4") (pintype "input"))
    )
    (net (code "64") (name "unconnected-(U3-I5-Pad5)") (class "Default")
      (node (ref "U3") (pin "5") (pinfunction "I5_5") (pintype "input"))
    )
    (net (code "65") (name "unconnected-(U3-I6-Pad6)") (class "Default")
      (node (ref "U3") (pin "6") (pinfunction "I6_6") (pintype "input"))
    )
    (net (code "66") (name "unconnected-(U3-I7-Pad7)") (class "Default")
      (node (ref "U3") (pin "7") (pinfunction "I7_7") (pintype "input"))
    )
    (net (code "67") (name "unconnected-(U3-O3-Pad14)") (class "Default")
      (node (ref "U3") (pin "14") (pinfunction "O3_14") (pintype "open_collector"))
    )
    (net (code "68") (name "unconnected-(U3-O4-Pad13)") (class "Default")
      (node (ref "U3") (pin "13") (pinfunction "O4_13") (pintype "open_collector"))
    )
    (net (code "69") (name "unconnected-(U3-O5-Pad12)") (class "Default")
      (node (ref "U3") (pin "12") (pinfunction "O5_12") (pintype "open_collector"))
    )
    (net (code "70") (name "unconnected-(U3-O6-Pad11)") (class "Default")
      (node (ref "U3") (pin "11") (pinfunction "O6_11") (pintype "open_collector"))
    )
    (net (code "71") (name "unconnected-(U3-O7-Pad10)") (class "Default")
      (node (ref "U3") (pin "10") (pinfunction "O7_10") (pintype "open_collector"))
    )
    (net (code "72") (name "unconnected-(U4-RA2{slash}AN2{slash}VREF-{slash}CVREF-Pad4)") (class "Default")
      (node (ref "U4") (pin "4") (pinfunction "RA2/AN2/VREF-/CVREF_4") (pintype "bidirectional"))
    )
    (net (code "73") (name "unconnected-(U4-RA3{slash}AN3{slash}VREF+{slash}VREF+-Pad5)") (class "Default")
      (node (ref "U4") (pin "5") (pinfunction "RA3/AN3/VREF+/VREF+_5") (pintype "bidirectional"))
    )
    (net (code "74") (name "unconnected-(U4-RA4{slash}T0CKI{slash}C1OUT-Pad6)") (class "Default")
      (node (ref "U4") (pin "6") (pinfunction "RA4/T0CKI/C1OUT_6") (pintype "bidirectional"))
    )
    (net (code "75") (name "unconnected-(U4-RA5{slash}AN4{slash}~SS{slash}C2OUT-Pad7)") (class "Default")
      (node (ref "U4") (pin "7") (pinfunction "RA5/AN4/~SS/C2OUT_7") (pintype "bidirectional"))
    )
    (net (code "76") (name "unconnected-(U4-RC2{slash}CCP1-Pad17)") (class "Default")
      (node (ref "U4") (pin "17") (pinfunction "RC2/CCP1_17") (pintype "bidirectional"))
    )
    (net (code "77") (name "unconnected-(U4-RC3{slash}SCK{slash}SCL-Pad18)") (class "Default")
      (node (ref "U4") (pin "18") (pinfunction "RC3/SCK/SCL_18") (pintype "bidirectional"))
    )
    (net (code "78") (name "unconnected-(U4-RC4{slash}SDI{slash}SDA-Pad23)") (class "Default")
      (node (ref "U4") (pin "23") (pinfunction "RC4/SDI/SDA_23") (pintype "bidirectional"))
    )
    (net (code "79") (name "unconnected-(U4-RC5{slash}SDO-Pad24)") (class "Default")
      (node (ref "U4") (pin "24") (pinfunction "RC5/SDO_24") (pintype "bidirectional"))
    )
    (net (code "80") (name "unconnected-(U4-RC6{slash}TX{slash}CK-Pad25)") (class "Default")
      (node (ref "U4") (pin "25") (pinfunction "RC6/TX/CK_25") (pintype "bidirectional"))
    )
    (net (code "81") (name "unconnected-(U4-RC7{slash}RX{slash}DT-Pad26)") (class "Default")
      (node (ref "U4") (pin "26") (pinfunction "RC7/RX/DT_26") (pintype "bidirectional"))
    )
    (net (code "82") (name "unconnected-(U4-RD5{slash}PSP5-Pad28)") (class "Default")
      (node (ref "U4") (pin "28") (pinfunction "RD5/PSP5_28") (pintype "bidirectional"))
    )
    (net (code "83") (name "unconnected-(U4-RD6{slash}PSP6-Pad29)") (class "Default")
      (node (ref "U4") (pin "29") (pinfunction "RD6/PSP6_29") (pintype "bidirectional"))
    )
    (net (code "84") (name "unconnected-(U4-RD7{slash}PSP7-Pad30)") (class "Default")
      (node (ref "U4") (pin "30") (pinfunction "RD7/PSP7_30") (pintype "bidirectional"))
    )
    (net (code "85") (name "unconnected-(U4-RE0{slash}~RD{slash}AN5-Pad8)") (class "Default")
      (node (ref "U4") (pin "8") (pinfunction "RE0/~RD/AN5_8") (pintype "bidirectional"))
    )
    (net (code "86") (name "unconnected-(U4-RE1{slash}~WR{slash}AN6-Pad9)") (class "Default")
      (node (ref "U4") (pin "9") (pinfunction "RE1/~WR/AN6_9") (pintype "bidirectional"))
    )
    (net (code "87") (name "unconnected-(U4-RE2{slash}~CS{slash}AN7-Pad10)") (class "Default")
      (node (ref "U4") (pin "10") (pinfunction "RE2/~CS/AN7_10") (pintype "bidirectional"))
    )
    (net (code "88") (name "unconnected-(U4-VSS-Pad31)") (class "Default")
      (node (ref "U4") (pin "31") (pinfunction "VSS_31") (pintype "power_in"))
    )
    (net (code "89") (name "unconnected-(U5-IN2(+)-Pad5)") (class "Default")
      (node (ref "U5") (pin "5") (pinfunction "IN2(+)_5") (pintype "input"))
    )
    (net (code "90") (name "unconnected-(U5-IN2(-)-Pad6)") (class "Default")
      (node (ref "U5") (pin "6") (pinfunction "IN2(-)_6") (pintype "input"))
    )
    (net (code "91") (name "unconnected-(U5-OUT2-Pad7)") (class "Default")
      (node (ref "U5") (pin "7") (pinfunction "OUT2_7") (pintype "output"))
    )
    (net (code "92") (name "x1") (class "Default")
      (node (ref "C1") (pin "1") (pinfunction "1_1") (pintype "passive"))
      (node (ref "U1") (pin "3") (pinfunction "Osc1_3") (pintype "passive"))
      (node (ref "U2") (pin "7") (pinfunction "X1_7") (pintype "bidirectional"))
      (node (ref "U4") (pin "13") (pinfunction "OSC1/CLKI_13") (pintype "input"))
      (node (ref "Y1") (pin "2") (pinfunction "OSC2_2") (pintype "passive"))
    )
    (net (code "93") (name "x2") (class "Default")
      (node (ref "C2") (pin "1") (pinfunction "1_1") (pintype "passive"))
      (node (ref "U1") (pin "4") (pinfunction "Osc0_4") (pintype "passive"))
      (node (ref "U2") (pin "8") (pinfunction "X2_8") (pintype "bidirectional"))
      (node (ref "U4") (pin "14") (pinfunction "OSC2/CLKO_14") (pintype "output"))
      (node (ref "Y1") (pin "1") (pinfunction "OSC1_1") (pintype "passive"))
    )
  )
)
